# conn_ffc_ws22_8pin.net
KiCad netlist of a schematic drawn in Altium Designer
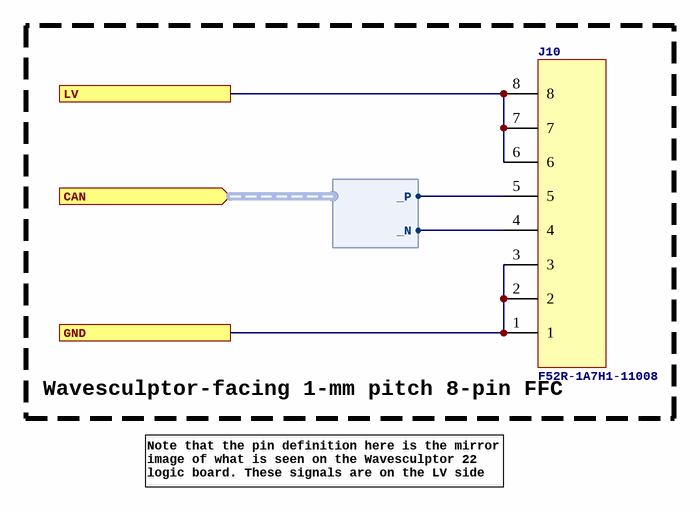
[diagram p0: conn_ffc_ws22_8pin.SchDoc]

(export (version "E")
  (design (tool "Eeschema 10.0.6"))
  (components
    (comp (ref "J10")
      (value "F52R-1A7H1-11008")
      (footprint "AMPHENOL_F52R-1A7H1-11008")
      (description "Conn, R/a, Ffc/fpc, 8POS, 1ROW, 1MM Rohs Compliant: Yes")
      (fields (field (name "MANUFACTURER") "Amphenol Communications Solutions"))
      (libsource (lib "SSCP") (part "CONN_AMPHENOL_FPC_F52R-1A7H1-11008"))
    )
  )
  (nets
    (net (code "2") (name "/GND") (class "Default")
      (node (ref "J10") (pin "1") (pinfunction "1_1") (pintype "passive"))
      (node (ref "J10") (pin "2") (pinfunction "2_2") (pintype "passive"))
      (node (ref "J10") (pin "3") (pinfunction "3_3") (pintype "passive"))
    )
    (net (code "3") (name "/LV") (class "Default")
      (node (ref "J10") (pin "6") (pinfunction "6_6") (pintype "passive"))
      (node (ref "J10") (pin "7") (pinfunction "7_7") (pintype "passive"))
      (node (ref "J10") (pin "8") (pinfunction "8_8") (pintype "passive"))
    )
    (net (code "4") (name "/_N") (class "Default")
      (node (ref "J10") (pin "4") (pinfunction "4_4") (pintype "passive"))
    )
    (net (code "5") (name "/_P") (class "Default")
      (node (ref "J10") (pin "5") (pinfunction "5_5") (pintype "passive"))
    )
  )
)
